# Thermocouple.net
KiCad netlist of a schematic drawn in Altium Designer
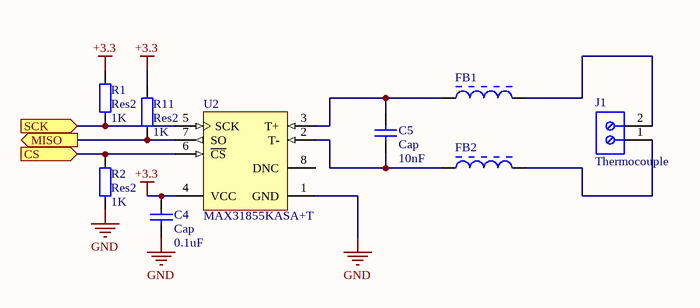
[diagram p0: Thermocouple.SchDoc]

(export (version "E")
  (design (tool "Eeschema 10.0.6"))
  (components
    (comp (ref "C4")
      (value "Cap")
      (footprint "1608[0603]")
      (description "Capacitor")
      (fields (field (name "ALTIUM_VALUE") "0.1uF") (field (name "PUBLISHER") "Altium Limited"))
      (libsource (lib "Miscellaneous Devices") (part "Cap"))
    )
    (comp (ref "C5")
      (value "Cap")
      (footprint "1608[0603]")
      (description "Capacitor")
      (fields (field (name "ALTIUM_VALUE") "10nF") (field (name "PUBLISHER") "Altium Limited"))
      (libsource (lib "Miscellaneous Devices") (part "Cap"))
    )
    (comp (ref "FB1")
      (value "BLM21AG102SN1D")
      (footprint "6-0805_M")
      (fields (field (name "MANUFACTURER") "Murata") (field (name "LCSC PART #") "C1015"))
      (libsource (lib "STM32F4_Breakout") (part "MURA-FB-2"))
    )
    (comp (ref "FB2")
      (value "BLM21AG102SN1D")
      (footprint "6-0805_M")
      (fields (field (name "MANUFACTURER") "Murata") (field (name "LCSC PART #") "C1015"))
      (libsource (lib "STM32F4_Breakout") (part "MURA-FB-2"))
    )
    (comp (ref "J1")
      (value "Thermocouple")
      (footprint "691137710002")
      (description "Series 1377 - 5.00 mm Horizontal Entry with Pressure Clamp WR-TBL, 2 pin")
      (fields
        (field (name "MANUFACTURER") "Wurth Elektronik")
        (field (name "PART NUMBER") "691137710002")
        (field (name "PUBLISHER") "WurthElektronik")
      )
      (libsource (lib "Altium Content Vault") (part "WE-CN-1P-F-TB2"))
    )
    (comp (ref "R1")
      (value "Res2")
      (footprint "J1-0603")
      (description "Resistor")
      (fields (field (name "ALTIUM_VALUE") "1K") (field (name "PUBLISHER") "Altium Limited"))
      (libsource (lib "Miscellaneous Devices") (part "Res2"))
    )
    (comp (ref "R2")
      (value "Res2")
      (footprint "J1-0603")
      (description "Resistor")
      (fields (field (name "ALTIUM_VALUE") "1K") (field (name "PUBLISHER") "Altium Limited"))
      (libsource (lib "Miscellaneous Devices") (part "Res2"))
    )
    (comp (ref "R11")
      (value "Res2")
      (footprint "J1-0603")
      (description "Resistor")
      (fields (field (name "ALTIUM_VALUE") "1K") (field (name "PUBLISHER") "Altium Limited"))
      (libsource (lib "Miscellaneous Devices") (part "Res2"))
    )
    (comp (ref "U2")
      (value "MAX31855KASA+T")
      (footprint "MAXM-S8+4_N")
      (fields (field (name "GENERIC PART NUMBER") "MAX31855"))
      (libsource (lib "Altium Content Vault") (part "MAX31855-S8+4"))
    )
  )
  (nets
    (net (code "1") (name "+3.3") (class "Default")
      (node (ref "C4") (pin "2") (pinfunction "2_2") (pintype "passive"))
      (node (ref "R1") (pin "2") (pinfunction "2_2") (pintype "passive"))
      (node (ref "R11") (pin "2") (pinfunction "2_2") (pintype "passive"))
      (node (ref "U2") (pin "4") (pinfunction "VCC_4") (pintype "power_in"))
    )
    (net (code "2") (name "/CS") (class "Default")
      (node (ref "R2") (pin "2") (pinfunction "2_2") (pintype "passive"))
      (node (ref "U2") (pin "6") (pinfunction "~{CS}_6") (pintype "input"))
    )
    (net (code "3") (name "/MISO") (class "Default")
      (node (ref "R11") (pin "1") (pinfunction "1_1") (pintype "passive"))
      (node (ref "U2") (pin "7") (pinfunction "SO_7") (pintype "output"))
    )
    (net (code "4") (name "/SCK") (class "Default")
      (node (ref "R1") (pin "1") (pinfunction "1_1") (pintype "passive"))
      (node (ref "U2") (pin "5") (pinfunction "SCK_5") (pintype "input"))
    )
    (net (code "5") (name "GND") (class "Default")
      (node (ref "C4") (pin "1") (pinfunction "1_1") (pintype "passive"))
      (node (ref "R2") (pin "1") (pinfunction "1_1") (pintype "passive"))
      (node (ref "U2") (pin "1") (pinfunction "GND_1") (pintype "power_in"))
    )
    (net (code "6") (name "Net-(FB1-Pad2)") (class "Default")
      (node (ref "FB1") (pin "2") (pinfunction "2_2") (pintype "passive"))
      (node (ref "J1") (pin "2") (pinfunction "2_2") (pintype "passive"))
    )
    (net (code "7") (name "Net-(FB2-Pad2)") (class "Default")
      (node (ref "FB2") (pin "2") (pinfunction "2_2") (pintype "passive"))
      (node (ref "J1") (pin "1") (pinfunction "1_1") (pintype "passive"))
    )
    (net (code "8") (name "Net-(U2-T+)") (class "Default")
      (node (ref "C5") (pin "2") (pinfunction "2_2") (pintype "passive"))
      (node (ref "FB1") (pin "1") (pinfunction "1_1") (pintype "passive"))
      (node (ref "U2") (pin "3") (pinfunction "T+_3") (pintype "input"))
    )
    (net (code "9") (name "Net-(U2-T-)") (class "Default")
      (node (ref "C5") (pin "1") (pinfunction "1_1") (pintype "passive"))
      (node (ref "FB2") (pin "1") (pinfunction "1_1") (pintype "passive"))
      (node (ref "U2") (pin "2") (pinfunction "T-_2") (pintype "input"))
    )
    (net (code "10") (name "unconnected-(U2-DNC-Pad8)") (class "Default")
      (node (ref "U2") (pin "8") (pinfunction "DNC_8") (pintype "passive"))
    )
  )
)
